# RWD_1Mb_RAM_Memory_CPC_v2_0.net
KiCad netlist of a schematic drawn in EAGLE
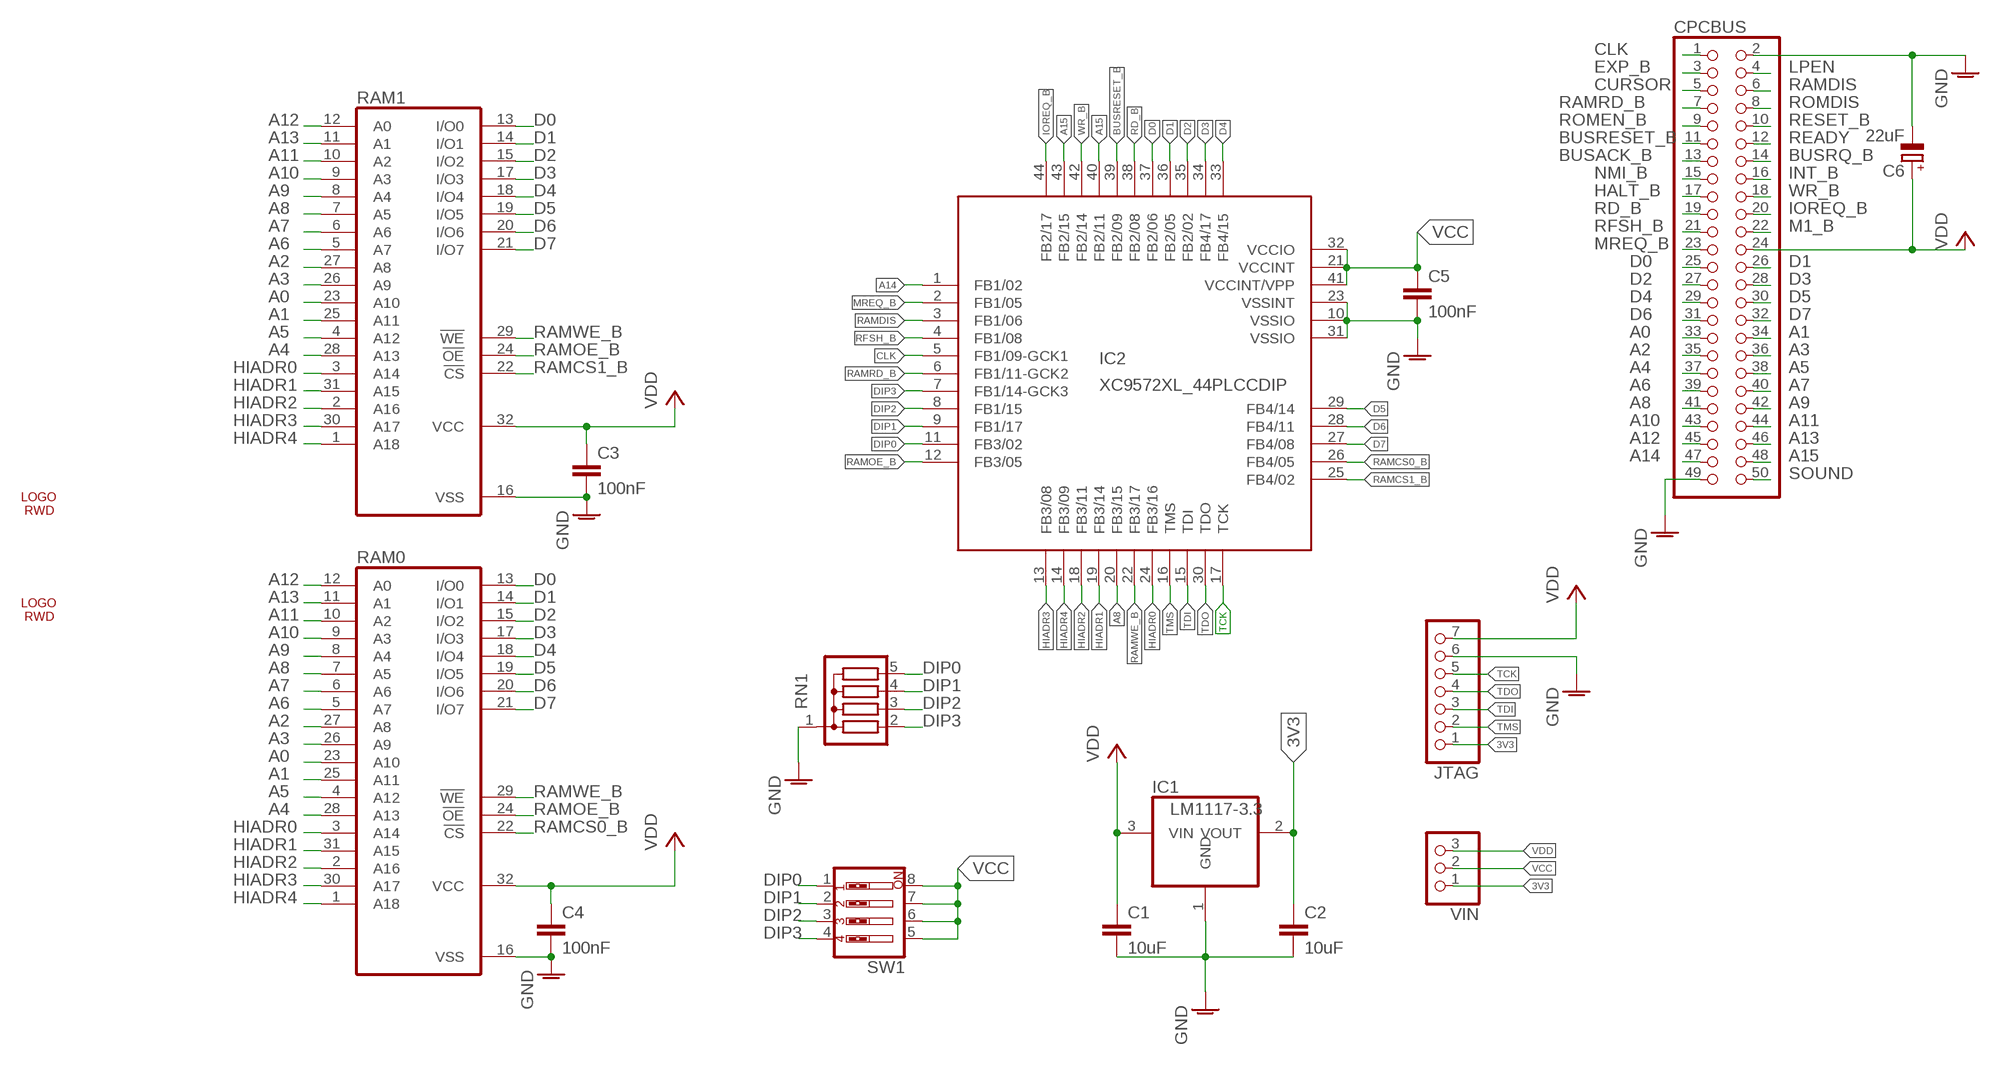
[diagram p0: schematic, sheet 1]

(export (version "E")
  (design (tool "Eeschema 10.0.6"))
  (components
    (comp (ref "C1")
      (value "10uF")
      (footprint "eagle-import:RCL_C0805")
      (libsource (lib "eagle-import") (part "RCL_C-EUC0805"))
    )
    (comp (ref "C2")
      (value "10uF")
      (footprint "eagle-import:RCL_C0805")
      (libsource (lib "eagle-import") (part "RCL_C-EUC0805"))
    )
    (comp (ref "C3")
      (value "100nF")
      (footprint "eagle-import:RCL_C0805")
      (libsource (lib "eagle-import") (part "RCL_C-EUC0805"))
    )
    (comp (ref "C4")
      (value "100nF")
      (footprint "eagle-import:RCL_C0805")
      (libsource (lib "eagle-import") (part "RCL_C-EUC0805"))
    )
    (comp (ref "C5")
      (value "100nF")
      (footprint "eagle-import:RCL_C0805")
      (libsource (lib "eagle-import") (part "RCL_C-EUC0805"))
    )
    (comp (ref "C6")
      (value "22uF")
      (footprint "eagle-import:E2-5")
      (libsource (lib "eagle-import") (part "CPOL-EUE2-5"))
    )
    (comp (ref "CPCBUS")
      (value "PINHEAD_PINHD-2X25")
      (footprint "eagle-import:PINHEAD_2X25")
      (libsource (lib "eagle-import") (part "PINHEAD_PINHD-2X25"))
    )
    (comp (ref "IC1")
      (value "LM1117-3.3")
      (footprint "eagle-import:BURR-BROWN_SOT223")
      (fields (field (name "MPN") "REG1117"))
      (libsource (lib "eagle-import") (part "BURR-BROWN_REG1117"))
    )
    (comp (ref "IC2")
      (value "XC9572XL_44PLCCDIP")
      (footprint "eagle-import:S44")
      (libsource (lib "eagle-import") (part "XC9572XL_44PLCCDIP"))
    )
    (comp (ref "JTAG")
      (value "PINHD-1X7")
      (footprint "eagle-import:1X07")
      (libsource (lib "eagle-import") (part "PINHD-1X7"))
    )
    (comp (ref "RAM0")
      (value "MEMORY-HITACHI_628512")
      (footprint "eagle-import:MEMORY-HITACHI_DIL32")
      (libsource (lib "eagle-import") (part "MEMORY-HITACHI_628512"))
    )
    (comp (ref "RAM1")
      (value "MEMORY-HITACHI_628512")
      (footprint "eagle-import:MEMORY-HITACHI_DIL32")
      (libsource (lib "eagle-import") (part "MEMORY-HITACHI_628512"))
    )
    (comp (ref "RN1")
      (value "G04R")
      (footprint "eagle-import:SIL5")
      (libsource (lib "eagle-import") (part "G04R"))
    )
    (comp (ref "SW1")
      (value "SW_DIP-4")
      (footprint "eagle-import:EDG-04")
      (libsource (lib "eagle-import") (part "SW_DIP-4"))
    )
    (comp (ref "U$1")
      (value "LOGO7TOP")
      (footprint "eagle-import:LOGO7_SK21")
      (libsource (lib "eagle-import") (part "LOGO7TOP"))
    )
    (comp (ref "U$2")
      (value "LOGO7TOP")
      (footprint "eagle-import:LOGO7_SK21")
      (libsource (lib "eagle-import") (part "LOGO7TOP"))
    )
    (comp (ref "VIN")
      (value "PINHD-1X3")
      (footprint "eagle-import:1X03")
      (libsource (lib "eagle-import") (part "PINHD-1X3"))
    )
  )
  (nets
    (net (code "1") (name "/A0") (class "Default")
      (node (ref "CPCBUS") (pin "33") (pinfunction "33_33") (pintype "passive"))
      (node (ref "RAM0") (pin "23") (pinfunction "A10_23") (pintype "input"))
      (node (ref "RAM1") (pin "23") (pinfunction "A10_23") (pintype "input"))
    )
    (net (code "2") (name "/A1") (class "Default")
      (node (ref "CPCBUS") (pin "34") (pinfunction "34_34") (pintype "passive"))
      (node (ref "RAM0") (pin "25") (pinfunction "A11_25") (pintype "input"))
      (node (ref "RAM1") (pin "25") (pinfunction "A11_25") (pintype "input"))
    )
    (net (code "3") (name "/A2") (class "Default")
      (node (ref "CPCBUS") (pin "35") (pinfunction "35_35") (pintype "passive"))
      (node (ref "RAM0") (pin "27") (pinfunction "A8_27") (pintype "input"))
      (node (ref "RAM1") (pin "27") (pinfunction "A8_27") (pintype "input"))
    )
    (net (code "4") (name "/A3") (class "Default")
      (node (ref "CPCBUS") (pin "36") (pinfunction "36_36") (pintype "passive"))
      (node (ref "RAM0") (pin "26") (pinfunction "A9_26") (pintype "input"))
      (node (ref "RAM1") (pin "26") (pinfunction "A9_26") (pintype "input"))
    )
    (net (code "5") (name "/A4") (class "Default")
      (node (ref "CPCBUS") (pin "37") (pinfunction "37_37") (pintype "passive"))
      (node (ref "RAM0") (pin "28") (pinfunction "A13_28") (pintype "input"))
      (node (ref "RAM1") (pin "28") (pinfunction "A13_28") (pintype "input"))
    )
    (net (code "6") (name "/A5") (class "Default")
      (node (ref "CPCBUS") (pin "38") (pinfunction "38_38") (pintype "passive"))
      (node (ref "RAM0") (pin "4") (pinfunction "A12_4") (pintype "input"))
      (node (ref "RAM1") (pin "4") (pinfunction "A12_4") (pintype "input"))
    )
    (net (code "7") (name "/A6") (class "Default")
      (node (ref "CPCBUS") (pin "39") (pinfunction "39_39") (pintype "passive"))
      (node (ref "RAM0") (pin "5") (pinfunction "A7_5") (pintype "input"))
      (node (ref "RAM1") (pin "5") (pinfunction "A7_5") (pintype "input"))
    )
    (net (code "8") (name "/A7") (class "Default")
      (node (ref "CPCBUS") (pin "40") (pinfunction "40_40") (pintype "passive"))
      (node (ref "RAM0") (pin "6") (pinfunction "A6_6") (pintype "input"))
      (node (ref "RAM1") (pin "6") (pinfunction "A6_6") (pintype "input"))
    )
    (net (code "9") (name "/A9") (class "Default")
      (node (ref "CPCBUS") (pin "42") (pinfunction "42_42") (pintype "passive"))
      (node (ref "RAM0") (pin "8") (pinfunction "A4_8") (pintype "input"))
      (node (ref "RAM1") (pin "8") (pinfunction "A4_8") (pintype "input"))
    )
    (net (code "10") (name "/A10") (class "Default")
      (node (ref "CPCBUS") (pin "43") (pinfunction "43_43") (pintype "passive"))
      (node (ref "RAM0") (pin "9") (pinfunction "A3_9") (pintype "input"))
      (node (ref "RAM1") (pin "9") (pinfunction "A3_9") (pintype "input"))
    )
    (net (code "11") (name "/A11") (class "Default")
      (node (ref "CPCBUS") (pin "44") (pinfunction "44_44") (pintype "passive"))
      (node (ref "RAM0") (pin "10") (pinfunction "A2_10") (pintype "input"))
      (node (ref "RAM1") (pin "10") (pinfunction "A2_10") (pintype "input"))
    )
    (net (code "12") (name "/A12") (class "Default")
      (node (ref "CPCBUS") (pin "45") (pinfunction "45_45") (pintype "passive"))
      (node (ref "RAM0") (pin "12") (pinfunction "A0_12") (pintype "input"))
      (node (ref "RAM1") (pin "12") (pinfunction "A0_12") (pintype "input"))
    )
    (net (code "13") (name "/A13") (class "Default")
      (node (ref "CPCBUS") (pin "46") (pinfunction "46_46") (pintype "passive"))
      (node (ref "RAM0") (pin "11") (pinfunction "A1_11") (pintype "input"))
      (node (ref "RAM1") (pin "11") (pinfunction "A1_11") (pintype "input"))
    )
    (net (code "14") (name "/BUSACK_B") (class "Default")
      (node (ref "CPCBUS") (pin "13") (pinfunction "13_13") (pintype "passive"))
    )
    (net (code "15") (name "/BUSRQ_B") (class "Default")
      (node (ref "CPCBUS") (pin "14") (pinfunction "14_14") (pintype "passive"))
    )
    (net (code "16") (name "/CURSOR") (class "Default")
      (node (ref "CPCBUS") (pin "5") (pinfunction "5_5") (pintype "passive"))
    )
    (net (code "17") (name "/EXP_B") (class "Default")
      (node (ref "CPCBUS") (pin "3") (pinfunction "3_3") (pintype "passive"))
    )
    (net (code "18") (name "/HALT_B") (class "Default")
      (node (ref "CPCBUS") (pin "17") (pinfunction "17_17") (pintype "passive"))
    )
    (net (code "19") (name "/INT_B") (class "Default")
      (node (ref "CPCBUS") (pin "16") (pinfunction "16_16") (pintype "passive"))
    )
    (net (code "20") (name "/LPEN") (class "Default")
      (node (ref "CPCBUS") (pin "4") (pinfunction "4_4") (pintype "passive"))
    )
    (net (code "21") (name "/M1_B") (class "Default")
      (node (ref "CPCBUS") (pin "22") (pinfunction "22_22") (pintype "passive"))
    )
    (net (code "22") (name "/NMI_B") (class "Default")
      (node (ref "CPCBUS") (pin "15") (pinfunction "15_15") (pintype "passive"))
    )
    (net (code "23") (name "/READY") (class "Default")
      (node (ref "CPCBUS") (pin "12") (pinfunction "12_12") (pintype "passive"))
    )
    (net (code "24") (name "/RESET_B") (class "Default")
      (node (ref "CPCBUS") (pin "10") (pinfunction "10_10") (pintype "passive"))
    )
    (net (code "25") (name "/ROMDIS") (class "Default")
      (node (ref "CPCBUS") (pin "8") (pinfunction "8_8") (pintype "passive"))
    )
    (net (code "26") (name "/ROMEN_B") (class "Default")
      (node (ref "CPCBUS") (pin "9") (pinfunction "9_9") (pintype "passive"))
    )
    (net (code "27") (name "/SOUND") (class "Default")
      (node (ref "CPCBUS") (pin "50") (pinfunction "50_50") (pintype "passive"))
    )
    (net (code "28") (name "3V3") (class "Default")
      (node (ref "C2") (pin "1") (pinfunction "1_1") (pintype "passive"))
      (node (ref "IC1") (pin "2") (pinfunction "VOUT_2") (pintype "output"))
      (node (ref "JTAG") (pin "1") (pinfunction "1_1") (pintype "passive"))
      (node (ref "VIN") (pin "1") (pinfunction "1_1") (pintype "passive"))
    )
    (net (code "29") (name "A8") (class "Default")
      (node (ref "CPCBUS") (pin "41") (pinfunction "41_41") (pintype "passive"))
      (node (ref "IC2") (pin "20") (pinfunction "FB3/15_20") (pintype "bidirectional"))
      (node (ref "RAM0") (pin "7") (pinfunction "A5_7") (pintype "input"))
      (node (ref "RAM1") (pin "7") (pinfunction "A5_7") (pintype "input"))
    )
    (net (code "30") (name "A14") (class "Default")
      (node (ref "CPCBUS") (pin "47") (pinfunction "47_47") (pintype "passive"))
      (node (ref "IC2") (pin "1") (pinfunction "FB1/02_1") (pintype "bidirectional"))
    )
    (net (code "31") (name "A15") (class "Default")
      (node (ref "CPCBUS") (pin "48") (pinfunction "48_48") (pintype "passive"))
      (node (ref "IC2") (pin "40") (pinfunction "FB2/11_40") (pintype "bidirectional"))
      (node (ref "IC2") (pin "43") (pinfunction "FB2/15_43") (pintype "bidirectional"))
    )
    (net (code "32") (name "BUSRESET_B") (class "Default")
      (node (ref "CPCBUS") (pin "11") (pinfunction "11_11") (pintype "passive"))
      (node (ref "IC2") (pin "39") (pinfunction "FB2/09_39") (pintype "bidirectional"))
    )
    (net (code "33") (name "CLK") (class "Default")
      (node (ref "CPCBUS") (pin "1") (pinfunction "1_1") (pintype "passive"))
      (node (ref "IC2") (pin "5") (pinfunction "FB1/09-GCK1_5") (pintype "bidirectional"))
    )
    (net (code "34") (name "D0") (class "Default")
      (node (ref "CPCBUS") (pin "25") (pinfunction "25_25") (pintype "passive"))
      (node (ref "IC2") (pin "37") (pinfunction "FB2/06_37") (pintype "bidirectional"))
      (node (ref "RAM0") (pin "13") (pinfunction "I/O0_13") (pintype "bidirectional"))
      (node (ref "RAM1") (pin "13") (pinfunction "I/O0_13") (pintype "bidirectional"))
    )
    (net (code "35") (name "D1") (class "Default")
      (node (ref "CPCBUS") (pin "26") (pinfunction "26_26") (pintype "passive"))
      (node (ref "IC2") (pin "36") (pinfunction "FB2/05_36") (pintype "bidirectional"))
      (node (ref "RAM0") (pin "14") (pinfunction "I/O1_14") (pintype "bidirectional"))
      (node (ref "RAM1") (pin "14") (pinfunction "I/O1_14") (pintype "bidirectional"))
    )
    (net (code "36") (name "D2") (class "Default")
      (node (ref "CPCBUS") (pin "27") (pinfunction "27_27") (pintype "passive"))
      (node (ref "IC2") (pin "35") (pinfunction "FB2/02_35") (pintype "bidirectional"))
      (node (ref "RAM0") (pin "15") (pinfunction "I/O2_15") (pintype "bidirectional"))
      (node (ref "RAM1") (pin "15") (pinfunction "I/O2_15") (pintype "bidirectional"))
    )
    (net (code "37") (name "D3") (class "Default")
      (node (ref "CPCBUS") (pin "28") (pinfunction "28_28") (pintype "passive"))
      (node (ref "IC2") (pin "34") (pinfunction "FB4/17_34") (pintype "bidirectional"))
      (node (ref "RAM0") (pin "17") (pinfunction "I/O3_17") (pintype "bidirectional"))
      (node (ref "RAM1") (pin "17") (pinfunction "I/O3_17") (pintype "bidirectional"))
    )
    (net (code "38") (name "D4") (class "Default")
      (node (ref "CPCBUS") (pin "29") (pinfunction "29_29") (pintype "passive"))
      (node (ref "IC2") (pin "33") (pinfunction "FB4/15_33") (pintype "bidirectional"))
      (node (ref "RAM0") (pin "18") (pinfunction "I/O4_18") (pintype "bidirectional"))
      (node (ref "RAM1") (pin "18") (pinfunction "I/O4_18") (pintype "bidirectional"))
    )
    (net (code "39") (name "D5") (class "Default")
      (node (ref "CPCBUS") (pin "30") (pinfunction "30_30") (pintype "passive"))
      (node (ref "IC2") (pin "29") (pinfunction "FB4/14_29") (pintype "bidirectional"))
      (node (ref "RAM0") (pin "19") (pinfunction "I/O5_19") (pintype "bidirectional"))
      (node (ref "RAM1") (pin "19") (pinfunction "I/O5_19") (pintype "bidirectional"))
    )
    (net (code "40") (name "D6") (class "Default")
      (node (ref "CPCBUS") (pin "31") (pinfunction "31_31") (pintype "passive"))
      (node (ref "IC2") (pin "28") (pinfunction "FB4/11_28") (pintype "bidirectional"))
      (node (ref "RAM0") (pin "20") (pinfunction "I/O6_20") (pintype "bidirectional"))
      (node (ref "RAM1") (pin "20") (pinfunction "I/O6_20") (pintype "bidirectional"))
    )
    (net (code "41") (name "D7") (class "Default")
      (node (ref "CPCBUS") (pin "32") (pinfunction "32_32") (pintype "passive"))
      (node (ref "IC2") (pin "27") (pinfunction "FB4/08_27") (pintype "bidirectional"))
      (node (ref "RAM0") (pin "21") (pinfunction "I/O7_21") (pintype "bidirectional"))
      (node (ref "RAM1") (pin "21") (pinfunction "I/O7_21") (pintype "bidirectional"))
    )
    (net (code "42") (name "DIP0") (class "Default")
      (node (ref "IC2") (pin "11") (pinfunction "FB3/02_11") (pintype "bidirectional"))
      (node (ref "RN1") (pin "5") (pinfunction "5_5") (pintype "passive"))
      (node (ref "SW1") (pin "1") (pinfunction "1_1") (pintype "passive"))
    )
    (net (code "43") (name "DIP1") (class "Default")
      (node (ref "IC2") (pin "9") (pinfunction "FB1/17_9") (pintype "bidirectional"))
      (node (ref "RN1") (pin "4") (pinfunction "4_4") (pintype "passive"))
      (node (ref "SW1") (pin "2") (pinfunction "2_2") (pintype "passive"))
    )
    (net (code "44") (name "DIP2") (class "Default")
      (node (ref "IC2") (pin "8") (pinfunction "FB1/15_8") (pintype "bidirectional"))
      (node (ref "RN1") (pin "3") (pinfunction "3_3") (pintype "passive"))
      (node (ref "SW1") (pin "3") (pinfunction "3_3") (pintype "passive"))
    )
    (net (code "45") (name "DIP3") (class "Default")
      (node (ref "IC2") (pin "7") (pinfunction "FB1/14-GCK3_7") (pintype "bidirectional"))
      (node (ref "RN1") (pin "2") (pinfunction "2_2") (pintype "passive"))
      (node (ref "SW1") (pin "4") (pinfunction "4_4") (pintype "passive"))
    )
    (net (code "46") (name "GND") (class "Default")
      (node (ref "C1") (pin "2") (pinfunction "2_2") (pintype "passive"))
      (node (ref "C2") (pin "2") (pinfunction "2_2") (pintype "passive"))
      (node (ref "C3") (pin "2") (pinfunction "2_2") (pintype "passive"))
      (node (ref "C4") (pin "2") (pinfunction "2_2") (pintype "passive"))
      (node (ref "C5") (pin "2") (pinfunction "2_2") (pintype "passive"))
      (node (ref "C6") (pin "-") (pinfunction "-_-") (pintype "passive"))
      (node (ref "CPCBUS") (pin "2") (pinfunction "2_2") (pintype "passive"))
      (node (ref "CPCBUS") (pin "49") (pinfunction "49_49") (pintype "passive"))
      (node (ref "IC1") (pin "1") (pinfunction "GND_1") (pintype "power_in"))
      (node (ref "IC2") (pin "10") (pinfunction "VSSIO_10") (pintype "power_in"))
      (node (ref "IC2") (pin "23") (pinfunction "VSSINT_23") (pintype "power_in"))
      (node (ref "IC2") (pin "31") (pinfunction "VSSIO_31") (pintype "power_in"))
      (node (ref "JTAG") (pin "6") (pinfunction "6_6") (pintype "passive"))
      (node (ref "RAM0") (pin "16") (pinfunction "VSS_16") (pintype "power_in"))
      (node (ref "RAM1") (pin "16") (pinfunction "VSS_16") (pintype "power_in"))
      (node (ref "RN1") (pin "1") (pinfunction "1_1") (pintype "passive"))
    )
    (net (code "47") (name "HIADR0") (class "Default")
      (node (ref "IC2") (pin "24") (pinfunction "FB3/16_24") (pintype "bidirectional"))
      (node (ref "RAM0") (pin "3") (pinfunction "A14_3") (pintype "input"))
      (node (ref "RAM1") (pin "3") (pinfunction "A14_3") (pintype "input"))
    )
    (net (code "48") (name "HIADR1") (class "Default")
      (node (ref "IC2") (pin "19") (pinfunction "FB3/14_19") (pintype "bidirectional"))
      (node (ref "RAM0") (pin "31") (pinfunction "A15_31") (pintype "input"))
      (node (ref "RAM1") (pin "31") (pinfunction "A15_31") (pintype "input"))
    )
    (net (code "49") (name "HIADR2") (class "Default")
      (node (ref "IC2") (pin "18") (pinfunction "FB3/11_18") (pintype "bidirectional"))
      (node (ref "RAM0") (pin "2") (pinfunction "A16_2") (pintype "input"))
      (node (ref "RAM1") (pin "2") (pinfunction "A16_2") (pintype "input"))
    )
    (net (code "50") (name "HIADR3") (class "Default")
      (node (ref "IC2") (pin "13") (pinfunction "FB3/08_13") (pintype "bidirectional"))
      (node (ref "RAM0") (pin "30") (pinfunction "A17_30") (pintype "input"))
      (node (ref "RAM1") (pin "30") (pinfunction "A17_30") (pintype "input"))
    )
    (net (code "51") (name "HIADR4") (class "Default")
      (node (ref "IC2") (pin "14") (pinfunction "FB3/09_14") (pintype "bidirectional"))
      (node (ref "RAM0") (pin "1") (pinfunction "A18_1") (pintype "input"))
      (node (ref "RAM1") (pin "1") (pinfunction "A18_1") (pintype "input"))
    )
    (net (code "52") (name "IOREQ_B") (class "Default")
      (node (ref "CPCBUS") (pin "20") (pinfunction "20_20") (pintype "passive"))
      (node (ref "IC2") (pin "44") (pinfunction "FB2/17_44") (pintype "bidirectional"))
    )
    (net (code "53") (name "MREQ_B") (class "Default")
      (node (ref "CPCBUS") (pin "23") (pinfunction "23_23") (pintype "passive"))
      (node (ref "IC2") (pin "2") (pinfunction "FB1/05_2") (pintype "bidirectional"))
    )
    (net (code "54") (name "RAMCS0_B") (class "Default")
      (node (ref "IC2") (pin "26") (pinfunction "FB4/05_26") (pintype "bidirectional"))
      (node (ref "RAM0") (pin "22") (pinfunction "~{CS}_22") (pintype "input"))
    )
    (net (code "55") (name "RAMCS1_B") (class "Default")
      (node (ref "IC2") (pin "25") (pinfunction "FB4/02_25") (pintype "bidirectional"))
      (node (ref "RAM1") (pin "22") (pinfunction "~{CS}_22") (pintype "input"))
    )
    (net (code "56") (name "RAMDIS") (class "Default")
      (node (ref "CPCBUS") (pin "6") (pinfunction "6_6") (pintype "passive"))
      (node (ref "IC2") (pin "3") (pinfunction "FB1/06_3") (pintype "bidirectional"))
    )
    (net (code "57") (name "RAMOE_B") (class "Default")
      (node (ref "IC2") (pin "12") (pinfunction "FB3/05_12") (pintype "bidirectional"))
      (node (ref "RAM0") (pin "24") (pinfunction "~{OE}_24") (pintype "input"))
      (node (ref "RAM1") (pin "24") (pinfunction "~{OE}_24") (pintype "input"))
    )
    (net (code "58") (name "RAMRD_B") (class "Default")
      (node (ref "CPCBUS") (pin "7") (pinfunction "7_7") (pintype "passive"))
      (node (ref "IC2") (pin "6") (pinfunction "FB1/11-GCK2_6") (pintype "bidirectional"))
    )
    (net (code "59") (name "RAMWE_B") (class "Default")
      (node (ref "IC2") (pin "22") (pinfunction "FB3/17_22") (pintype "bidirectional"))
      (node (ref "RAM0") (pin "29") (pinfunction "~{WE}_29") (pintype "input"))
      (node (ref "RAM1") (pin "29") (pinfunction "~{WE}_29") (pintype "input"))
    )
    (net (code "60") (name "RD_B") (class "Default")
      (node (ref "CPCBUS") (pin "19") (pinfunction "19_19") (pintype "passive"))
      (node (ref "IC2") (pin "38") (pinfunction "FB2/08_38") (pintype "bidirectional"))
    )
    (net (code "61") (name "RFSH_B") (class "Default")
      (node (ref "CPCBUS") (pin "21") (pinfunction "21_21") (pintype "passive"))
      (node (ref "IC2") (pin "4") (pinfunction "FB1/08_4") (pintype "bidirectional"))
    )
    (net (code "62") (name "TCK") (class "Default")
      (node (ref "IC2") (pin "17") (pinfunction "TCK_17") (pintype "input"))
      (node (ref "JTAG") (pin "5") (pinfunction "5_5") (pintype "passive"))
    )
    (net (code "63") (name "TDI") (class "Default")
      (node (ref "IC2") (pin "15") (pinfunction "TDI_15") (pintype "input"))
      (node (ref "JTAG") (pin "3") (pinfunction "3_3") (pintype "passive"))
    )
    (net (code "64") (name "TDO") (class "Default")
      (node (ref "IC2") (pin "30") (pinfunction "TDO_30") (pintype "output"))
      (node (ref "JTAG") (pin "4") (pinfunction "4_4") (pintype "passive"))
    )
    (net (code "65") (name "TMS") (class "Default")
      (node (ref "IC2") (pin "16") (pinfunction "TMS_16") (pintype "input"))
      (node (ref "JTAG") (pin "2") (pinfunction "2_2") (pintype "passive"))
    )
    (net (code "66") (name "VCC") (class "Default")
      (node (ref "C5") (pin "1") (pinfunction "1_1") (pintype "passive"))
      (node (ref "IC2") (pin "21") (pinfunction "VCCINT_21") (pintype "power_in"))
      (node (ref "IC2") (pin "32") (pinfunction "VCCIO_32") (pintype "power_in"))
      (node (ref "IC2") (pin "41") (pinfunction "VCCINT/VPP_41") (pintype "input"))
      (node (ref "SW1") (pin "5") (pinfunction "5_5") (pintype "passive"))
      (node (ref "SW1") (pin "6") (pinfunction "6_6") (pintype "passive"))
      (node (ref "SW1") (pin "7") (pinfunction "7_7") (pintype "passive"))
      (node (ref "SW1") (pin "8") (pinfunction "8_8") (pintype "passive"))
      (node (ref "VIN") (pin "2") (pinfunction "2_2") (pintype "passive"))
    )
    (net (code "67") (name "VDD") (class "Default")
      (node (ref "C1") (pin "1") (pinfunction "1_1") (pintype "passive"))
      (node (ref "C3") (pin "1") (pinfunction "1_1") (pintype "passive"))
      (node (ref "C4") (pin "1") (pinfunction "1_1") (pintype "passive"))
      (node (ref "C6") (pin "+") (pinfunction "+_+") (pintype "passive"))
      (node (ref "CPCBUS") (pin "24") (pinfunction "24_24") (pintype "passive"))
      (node (ref "IC1") (pin "3") (pinfunction "VIN_3") (pintype "input"))
      (node (ref "JTAG") (pin "7") (pinfunction "7_7") (pintype "passive"))
      (node (ref "RAM0") (pin "32") (pinfunction "VCC_32") (pintype "power_in"))
      (node (ref "RAM1") (pin "32") (pinfunction "VCC_32") (pintype "power_in"))
      (node (ref "VIN") (pin "3") (pinfunction "3_3") (pintype "passive"))
    )
    (net (code "68") (name "WR_B") (class "Default")
      (node (ref "CPCBUS") (pin "18") (pinfunction "18_18") (pintype "passive"))
      (node (ref "IC2") (pin "42") (pinfunction "FB2/14_42") (pintype "bidirectional"))
    )
  )
)
